# USB_POWER.net
KiCad netlist of a schematic drawn in Altium Designer
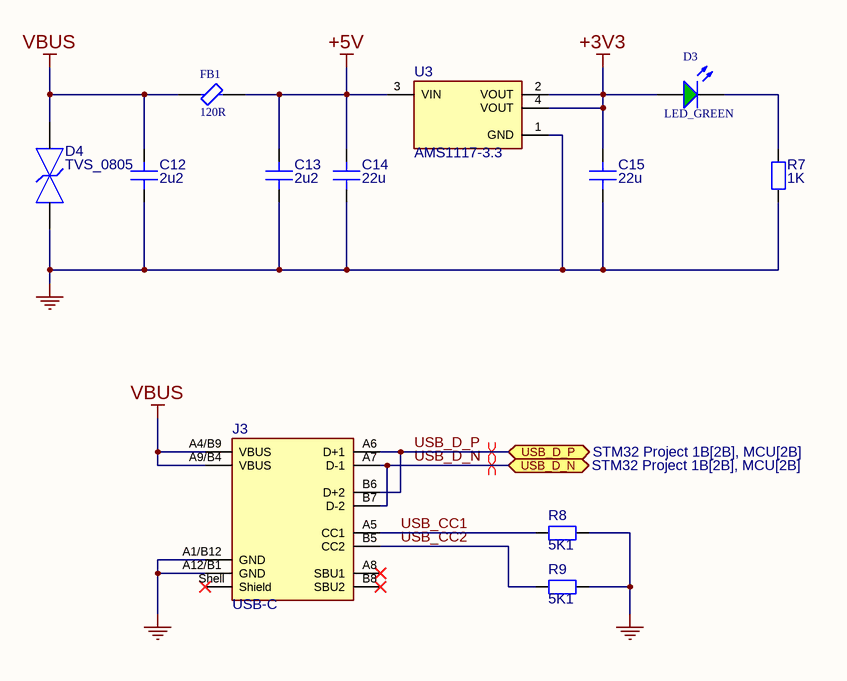
[diagram p0: USB_POWER.SchDoc]

(export (version "E")
  (design (tool "Eeschema 10.0.6"))
  (components
    (comp (ref "C12")
      (value "2u2")
      (footprint "CAP_0805")
      (description "Capacitor SMD 0805 Generic")
      (libsource (lib "Generic-Schematic-Library") (part "CAP_0805"))
    )
    (comp (ref "C13")
      (value "2u2")
      (footprint "CAP_0805")
      (description "Capacitor SMD 0805 Generic")
      (libsource (lib "Generic-Schematic-Library") (part "CAP_0805"))
    )
    (comp (ref "C14")
      (value "22u")
      (footprint "CAP_0805")
      (description "Capacitor SMD 0805 Generic")
      (libsource (lib "Generic-Schematic-Library") (part "CAP_0805"))
    )
    (comp (ref "C15")
      (value "22u")
      (footprint "CAP_0805")
      (description "Capacitor SMD 0805 Generic")
      (libsource (lib "Generic-Schematic-Library") (part "CAP_0805"))
    )
    (comp (ref "D3")
      (value "LED_GREEN")
      (footprint "LED_GREEN_0805")
      (description "Chip LED, Green, 2.2 V, -40 to 85 degC, 2-Pin SMD, Pb-Free, Tape and Reel")
      (fields (field (name "MANUFACTURER") "Avago"))
      (libsource (lib "Generic-Schematic-Library") (part "LED_GREEN_0805"))
    )
    (comp (ref "D4")
      (value "TVS_0805")
      (footprint "TVS_0805")
      (description "ESD Suppressor SMD 0805")
      (fields
        (field (name "MANUFACTURER") "Panasonic")
        (field (name "OCTOPART") "https://octopart.com/eza-eg2a50ax-panasonic-39557977")
      )
      (libsource (lib "Generic-Schematic-Library") (part "TVS_0805"))
    )
    (comp (ref "FB1")
      (value "120R")
      (footprint "FERRITE_BEAD_0805")
      (description "FERRITE BEAD 120 OHM 0805 1LN")
      (fields (field (name "TOLERANCE") "25%"))
      (libsource (lib "Generic-Schematic-Library") (part "FERRITE_BEAD_0805"))
    )
    (comp (ref "J3")
      (value "USB-C")
      (footprint "USB-C SMD 16 Pin")
      (description "Usb Conn, 2.0 Type C, R/A Rcpt, 16P, Smt Rohs Compliant: Yes ¦Wurth Elektronik 629722000214")
      (fields
        (field (name "MANUFACTURER") "Wurth Electronics")
        (field (name "MANUFACTURER PART NUMBER") "629722000214")
      )
      (libsource (lib "Generic-Schematic-Library") (part "USB-C SMD 16 Pin"))
    )
    (comp (ref "R7")
      (value "1K")
      (footprint "RES_0402")
      (description "Resistor SMD 0805 Generic")
      (libsource (lib "Generic-Schematic-Library") (part "RES_0805"))
    )
    (comp (ref "R8")
      (value "5K1")
      (footprint "RES_0805")
      (description "Resistor SMD 0805 Generic")
      (libsource (lib "Generic-Schematic-Library") (part "RES_0805"))
    )
    (comp (ref "R9")
      (value "5K1")
      (footprint "RES_0805")
      (description "Resistor SMD 0805 Generic")
      (libsource (lib "Generic-Schematic-Library") (part "RES_0805"))
    )
    (comp (ref "U3")
      (value "AMS1117-3.3")
      (footprint "AMS1117-3.3")
      (description "LDO Voltage Regulators 1A, 3.3V")
      (fields
        (field (name "OCTOPART") "https://octopart.com/ams1117-3.3-advanced+monolithic+systems-25899300")
        (field (name "MANUFACTURER") "Advanced Monolithic Systems")
      )
      (libsource (lib "Generic-Schematic-Library") (part "AMS1117-3.3"))
    )
  )
  (nets
    (net (code "1") (name "+3V3") (class "Default")
      (node (ref "C15") (pin "2") (pintype "passive"))
      (node (ref "D3") (pin "1") (pinfunction "A_1") (pintype "passive"))
      (node (ref "U3") (pin "2") (pinfunction "VOUT_2") (pintype "passive"))
      (node (ref "U3") (pin "4") (pinfunction "VOUT_4") (pintype "passive"))
    )
    (net (code "2") (name "+5V") (class "Default")
      (node (ref "C13") (pin "2") (pintype "passive"))
      (node (ref "C14") (pin "2") (pintype "passive"))
      (node (ref "FB1") (pin "2") (pinfunction "2_2") (pintype "passive"))
      (node (ref "U3") (pin "3") (pinfunction "VIN_3") (pintype "power_in"))
    )
    (net (code "3") (name "/USB_CC1") (class "Default")
      (node (ref "J3") (pin "A5") (pinfunction "CC1_A5") (pintype "passive"))
      (node (ref "R8") (pin "1") (pintype "passive"))
    )
    (net (code "4") (name "/USB_CC2") (class "Default")
      (node (ref "J3") (pin "B5") (pinfunction "CC2_B5") (pintype "passive"))
      (node (ref "R9") (pin "1") (pintype "passive"))
    )
    (net (code "5") (name "/USB_D_N") (class "Default")
      (node (ref "J3") (pin "A7") (pinfunction "D-1_A7") (pintype "passive"))
      (node (ref "J3") (pin "B7") (pinfunction "D-2_B7") (pintype "passive"))
    )
    (net (code "6") (name "/USB_D_P") (class "Default")
      (node (ref "J3") (pin "A6") (pinfunction "D+1_A6") (pintype "passive"))
      (node (ref "J3") (pin "B6") (pinfunction "D+2_B6") (pintype "passive"))
    )
    (net (code "7") (name "GND") (class "Default")
      (node (ref "C12") (pin "1") (pintype "passive"))
      (node (ref "C13") (pin "1") (pintype "passive"))
      (node (ref "C14") (pin "1") (pintype "passive"))
      (node (ref "C15") (pin "1") (pintype "passive"))
      (node (ref "D4") (pin "1") (pinfunction "1_1") (pintype "passive"))
      (node (ref "J3") (pin "A1/B12") (pinfunction "GND_A1/B12") (pintype "passive"))
      (node (ref "J3") (pin "A12/B1") (pinfunction "GND_A12/B1") (pintype "passive"))
      (node (ref "R7") (pin "1") (pintype "passive"))
      (node (ref "R8") (pin "2") (pintype "passive"))
      (node (ref "R9") (pin "2") (pintype "passive"))
      (node (ref "U3") (pin "1") (pinfunction "GND_1") (pintype "power_in"))
    )
    (net (code "8") (name "Net-(D3-K)") (class "Default")
      (node (ref "D3") (pin "2") (pinfunction "K_2") (pintype "passive"))
      (node (ref "R7") (pin "2") (pintype "passive"))
    )
    (net (code "9") (name "VBUS") (class "Default")
      (node (ref "C12") (pin "2") (pintype "passive"))
      (node (ref "D4") (pin "2") (pinfunction "2_2") (pintype "passive"))
      (node (ref "FB1") (pin "1") (pinfunction "1_1") (pintype "passive"))
      (node (ref "J3") (pin "A4/B9") (pinfunction "VBUS_A4/B9") (pintype "passive"))
      (node (ref "J3") (pin "A9/B4") (pinfunction "VBUS_A9/B4") (pintype "passive"))
    )
    (net (code "10") (name "unconnected-(J3-SBU1-PadA8)") (class "Default")
      (node (ref "J3") (pin "A8") (pinfunction "SBU1_A8") (pintype "passive+no_connect"))
    )
    (net (code "11") (name "unconnected-(J3-SBU2-PadB8)") (class "Default")
      (node (ref "J3") (pin "B8") (pinfunction "SBU2_B8") (pintype "passive+no_connect"))
    )
    (net (code "12") (name "unconnected-(J3-Shield-PadShell)") (class "Default")
      (node (ref "J3") (pin "Shell") (pinfunction "Shield_Shell") (pintype "passive+no_connect"))
    )
  )
)
